# Voltage_Source.net
KiCad netlist of a schematic drawn in Altium Designer
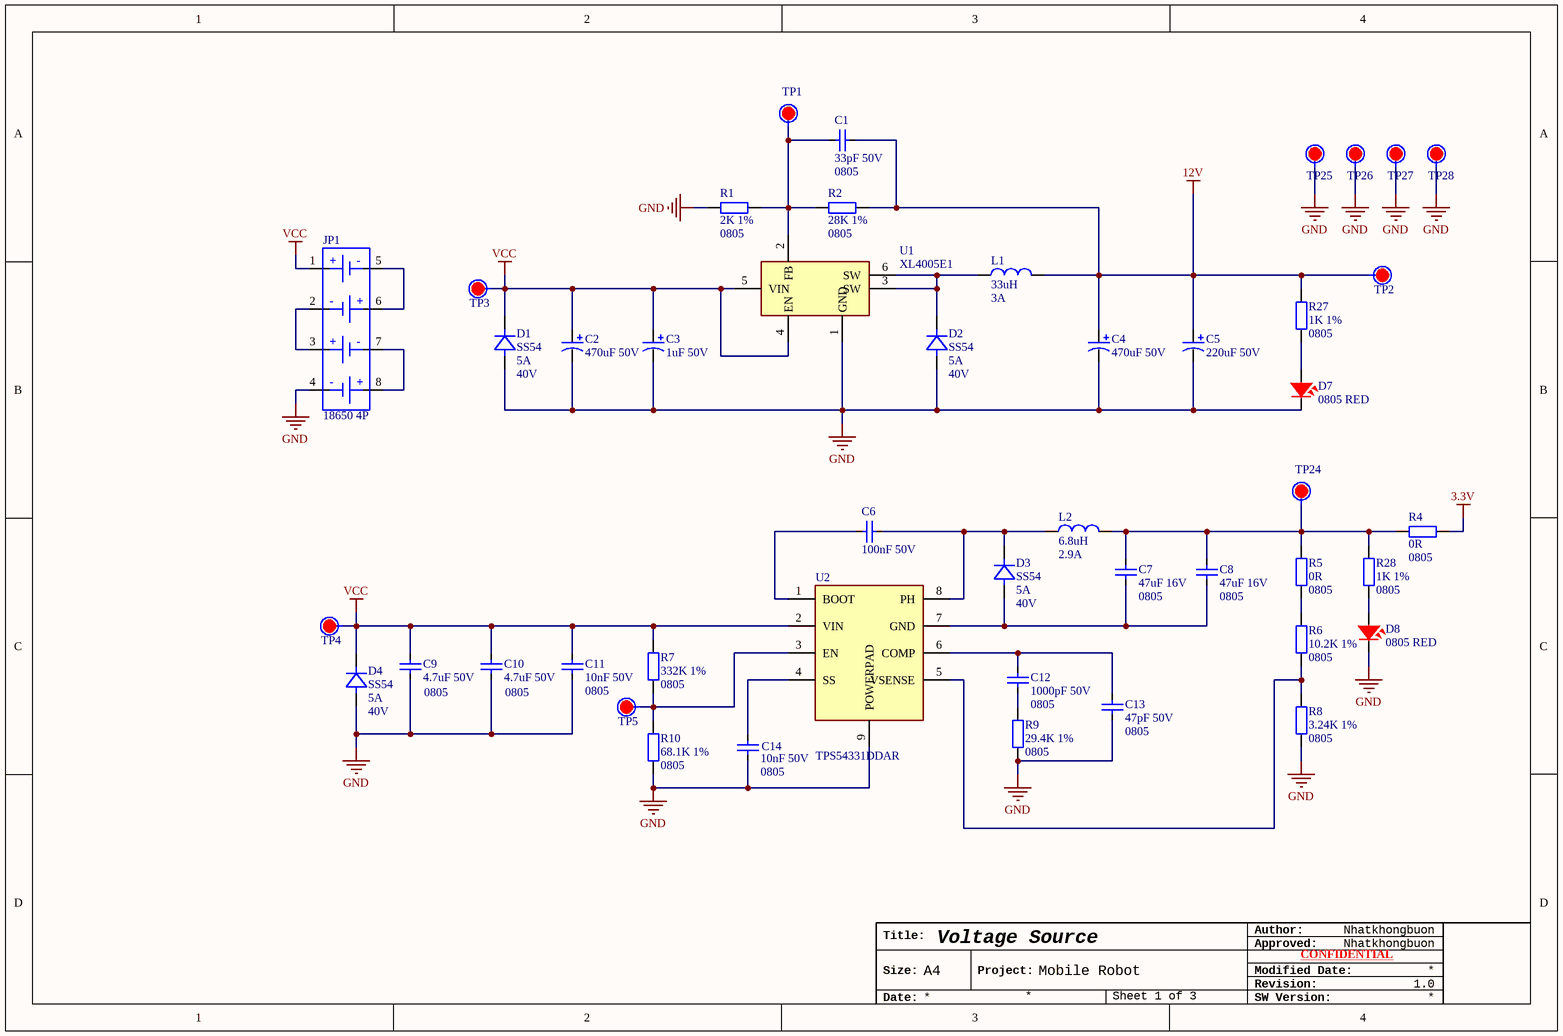
[diagram p0: Voltage Source.SchDoc]

(export (version "E")
  (design (tool "Eeschema 10.0.6"))
  (components
    (comp (ref "C1")
      (value "33pF 50V")
      (footprint "CAP_SMD_0805_NEW")
      (description "33 pF ±10% 50V Ceramic Capacitor C0G, NP0 0805 (2012 Metric)")
      (fields
        (field (name "MANUFACTURER") "KEMET")
        (field (name "MANUFACTURE PART NUMBER") "C0805C330K5GAC7800")
        (field (name "SIZE") "0805")
      )
      (libsource (lib "Capacitors") (part "C0805_MLCC_33pF_50V"))
    )
    (comp (ref "C2")
      (value "470uF 50V")
      (footprint "CAP-ALU-SMD-D12.5xL13.5")
      (description "470uF 50V ±20% SMD,D12.5xL13.5mm Aluminum Electrolytic Capacitors - SMD ROHS")
      (fields
        (field (name "MANUFACTURER") "Changzhou Huawei Elec")
        (field (name "MANUFACTURE PART NUMBER") "VT1H471MI135000CE0")
      )
      (libsource (lib "Capacitors") (part "C_ALU_470uF_50V"))
    )
    (comp (ref "C3")
      (value "1uF 50V")
      (footprint "CAP-ALU-SMD-B -NEW")
      (description "1uF 50V 7mA@120Hz ±20% SMD,D4xL5.4mm Aluminum Electrolytic Capacitors - SMD ROHS")
      (fields (field (name "MANUFACTURER") "KNSCHA") (field (name "MANUFACTURE PART NUMBER") "RST1UF50V017"))
      (libsource (lib "Capacitors") (part "C_ALU_1uF_50V_B"))
    )
    (comp (ref "C4")
      (value "470uF 50V")
      (footprint "CAP-ALU-SMD-D12.5xL13.5")
      (description "470uF 50V ±20% SMD,D12.5xL13.5mm Aluminum Electrolytic Capacitors - SMD ROHS")
      (fields
        (field (name "MANUFACTURER") "Changzhou Huawei Elec")
        (field (name "MANUFACTURE PART NUMBER") "VT1H471MI135000CE0")
      )
      (libsource (lib "Capacitors") (part "C_ALU_470uF_50V"))
    )
    (comp (ref "C5")
      (value "220uF 50V")
      (footprint "CAP-ALU-SMD-G-NEW")
      (description "220uF 50V 220mA@120Hz ±20% SMD,D10xL10.5mm Aluminum Electrolytic Capacitors - SMD ROHS")
      (fields
        (field (name "MANUFACTURER") "KNSCHA")
        (field (name "MANUFACTURE PART NUMBER") "XT220UF50V90RV0078")
      )
      (libsource (lib "Capacitors") (part "C_ALU_220uF_50V_G"))
    )
    (comp (ref "C6")
      (value "100nF 50V")
      (footprint "CAP_SMD_0805_NEW")
      (description "0.1 µF ±10% 50V Ceramic Capacitor X7R 0805 (2012 Metric)")
      (fields
        (field (name "MANUFACTURER") "YAGEO")
        (field (name "MANUFACTURE PART NUMBER") "CC0805KRX7R9BB104")
      )
      (libsource (lib "Capacitors") (part "C0805_MLCC_100nF_50V"))
    )
    (comp (ref "C7")
      (value "47uF 16V")
      (footprint "CAP_SMD_0805_NEW")
      (description "47 µF ±10% 16V Ceramic Capacitor X5R 1210 (3225 Metric)")
      (fields
        (field (name "MANUFACTURER") "Samsung Electro-Mechanics")
        (field (name "MANUFACTURE PART NUMBER") "CL32A476KOJNNNE")
        (field (name "SIZE") "0805")
      )
      (libsource (lib "Capacitors") (part "C0805_MLCC_47uF_16V"))
    )
    (comp (ref "C8")
      (value "47uF 16V")
      (footprint "CAP_SMD_0805_NEW")
      (description "47 µF ±10% 16V Ceramic Capacitor X5R 1210 (3225 Metric)")
      (fields
        (field (name "MANUFACTURER") "Samsung Electro-Mechanics")
        (field (name "MANUFACTURE PART NUMBER") "CL32A476KOJNNNE")
        (field (name "SIZE") "0805")
      )
      (libsource (lib "Capacitors") (part "C0805_MLCC_47uF_16V"))
    )
    (comp (ref "C9")
      (value "4.7uF 50V")
      (footprint "CAP_SMD_0805_NEW")
      (description "4.7 µF ±10% 50V Ceramic Capacitor X5R 0805 (2012 Metric)")
      (fields
        (field (name "MANUFACTURER") "Samsung Electro-Mechanics")
        (field (name "MANUFACTURE PART NUMBER") "CL21A475KBQNNNE")
        (field (name "SIZE") "0805")
      )
      (libsource (lib "Capacitors") (part "C0805_MLCC_4.7uF_50V"))
    )
    (comp (ref "C10")
      (value "4.7uF 50V")
      (footprint "CAP_SMD_0805_NEW")
      (description "4.7 µF ±10% 50V Ceramic Capacitor X5R 0805 (2012 Metric)")
      (fields
        (field (name "MANUFACTURER") "Samsung Electro-Mechanics")
        (field (name "MANUFACTURE PART NUMBER") "CL21A475KBQNNNE")
        (field (name "SIZE") "0805")
      )
      (libsource (lib "Capacitors") (part "C0805_MLCC_4.7uF_50V"))
    )
    (comp (ref "C11")
      (value "10nF 50V")
      (footprint "CAP_SMD_0805_NEW")
      (description "10000 pF ±10% 50V Ceramic Capacitor X7R 0805 (2012 Metric)")
      (fields
        (field (name "MANUFACTURER") "Samsung Electro-Mechanics")
        (field (name "MANUFACTURE PART NUMBER") "CL21B103KBANNNC")
        (field (name "SIZE") "0805")
      )
      (libsource (lib "Capacitors") (part "C0805_MLCC_10nF_50V"))
    )
    (comp (ref "C12")
      (value "1000pF 50V")
      (footprint "CAP_SMD_0805_NEW")
      (description "1000 pF ±10% 50V Ceramic Capacitor X7R 0805 (2012 Metric)")
      (fields
        (field (name "MANUFACTURER") "KEMET")
        (field (name "MANUFACTURE PART NUMBER") "C0805C102K5RAC7800")
        (field (name "SIZE") "0805")
      )
      (libsource (lib "Capacitors") (part "C0805_MLCC_1000pF_50V"))
    )
    (comp (ref "C13")
      (value "47pF 50V")
      (footprint "CAP_SMD_0805_NEW")
      (description "47 pF ±5% 50V Ceramic Capacitor C0G, NP0 0805 (2012 Metric)")
      (fields
        (field (name "MANUFACTURER") "YAGEO")
        (field (name "MANUFACTURE PART NUMBER") "CC0805JRNPO9BN470")
        (field (name "SIZE") "0805")
      )
      (libsource (lib "Capacitors") (part "C0805_MLCC_47pF_50V"))
    )
    (comp (ref "C14")
      (value "10nF 50V")
      (footprint "CAP_SMD_0805_NEW")
      (description "10000 pF ±10% 50V Ceramic Capacitor X7R 0805 (2012 Metric)")
      (fields
        (field (name "MANUFACTURER") "Samsung Electro-Mechanics")
        (field (name "MANUFACTURE PART NUMBER") "CL21B103KBANNNC")
        (field (name "SIZE") "0805")
      )
      (libsource (lib "Capacitors") (part "C0805_MLCC_10nF_50V"))
    )
    (comp (ref "D1")
      (value "SS54")
      (footprint "SMA")
      (description "DIODE SCHOTTKY 40V 5A SMA")
      (fields
        (field (name "MANUFACTURER") "EVVO")
        (field (name "CURRENT") "5A")
        (field (name "DC VOLTAGE") "40V")
      )
      (libsource (lib "Diode") (part "SS54"))
    )
    (comp (ref "D2")
      (value "SS54")
      (footprint "SMA")
      (description "DIODE SCHOTTKY 40V 5A SMA")
      (fields
        (field (name "MANUFACTURER") "EVVO")
        (field (name "CURRENT") "5A")
        (field (name "DC VOLTAGE") "40V")
      )
      (libsource (lib "Diode") (part "SS54"))
    )
    (comp (ref "D3")
      (value "SS54")
      (footprint "SMA")
      (description "DIODE SCHOTTKY 40V 5A SMA")
      (fields
        (field (name "MANUFACTURER") "EVVO")
        (field (name "CURRENT") "5A")
        (field (name "DC VOLTAGE") "40V")
      )
      (libsource (lib "Diode") (part "SS54"))
    )
    (comp (ref "D4")
      (value "SS54")
      (footprint "SMA")
      (description "DIODE SCHOTTKY 40V 5A SMA")
      (fields
        (field (name "MANUFACTURER") "EVVO")
        (field (name "CURRENT") "5A")
        (field (name "DC VOLTAGE") "40V")
      )
      (libsource (lib "Diode") (part "SS54"))
    )
    (comp (ref "D7")
      (value "0805 RED")
      (footprint "LED-0805-Red")
      (description "Red 625nm LED Indication - Discrete 2V 0805 (2012 Metric)")
      (fields
        (field (name "MANUFACTURER") "Würth Elektronik")
        (field (name "MANUFACTURE PART NUMBER") "150080RS75000")
      )
      (libsource (lib "LEDs") (part "LED_0805_RED"))
    )
    (comp (ref "D8")
      (value "0805 RED")
      (footprint "LED-0805-Red")
      (description "Red 625nm LED Indication - Discrete 2V 0805 (2012 Metric)")
      (fields
        (field (name "MANUFACTURER") "Würth Elektronik")
        (field (name "MANUFACTURE PART NUMBER") "150080RS75000")
      )
      (libsource (lib "LEDs") (part "LED_0805_RED"))
    )
    (comp (ref "JP1")
      (value "18650 4P")
      (footprint "18650 Holder 4P")
      (description "18650 Holder 4P")
      (libsource (lib "Connectors") (part "18650_HLD_4P"))
    )
    (comp (ref "L1")
      (value "33uH 3A")
      (footprint "L_TOR_13x7")
      (description "Toroidal Coil Inductor 33uH 3A")
      (fields (field (name "INDUCTOR") "33uH") (field (name "CURRENT") "3A"))
      (libsource (lib "Inductors") (part "L_33uH_3A"))
    )
    (comp (ref "L2")
      (value "CD74R_6.8uH")
      (footprint "CD74R")
      (description "2.9A 6.8uH ±30% SMD,7.5x7.5mm Power Inductors ROHS")
      (fields
        (field (name "MANUFACTURER") "SHOU HAN")
        (field (name "MANUFACTURE PART NUMBER") "CYH74-6.8UH")
        (field (name "INDUCTOR") "6.8uH")
        (field (name "CURRENT") "2.9A")
      )
      (libsource (lib "Inductors") (part "CD74R_6.8uH"))
    )
    (comp (ref "R1")
      (value "2K 1%")
      (footprint "RES_SMD_0805")
      (description "2 kOhms ±1% 0.125W, 1/8W Chip Resistor 0805 (2012 Metric) Automotive AEC-Q200 Thick Film")
      (fields
        (field (name "MANUFACTURER") "Panasonic Electronic Components")
        (field (name "MANUFACTURE PART NUMBER") "ERJ-6ENF2001V")
        (field (name "SIZE") "0805")
      )
      (libsource (lib "Resistors") (part "R0805_2K"))
    )
    (comp (ref "R2")
      (value "28K 1%")
      (footprint "RES_SMD_0805")
      (description "28 kOhms ±1% 0.125W, 1/8W Chip Resistor 0805 (2012 Metric) Moisture Resistant Thick Film")
      (fields
        (field (name "MANUFACTURER") "YAGEO")
        (field (name "MANUFACTURE PART NUMBER") "RC0805FR-0728KL")
        (field (name "SIZE") "0805")
      )
      (libsource (lib "Resistors") (part "R0805_28K"))
    )
    (comp (ref "R4")
      (value "0R")
      (footprint "RES_SMD_0805")
      (description "0 Ohms Jumper Chip Resistor 0805 (2012 Metric) Automotive AEC-Q200 Thick Film")
      (fields
        (field (name "MANUFACTURER") "Vishay Dale")
        (field (name "MANUFACTURE PART NUMBER") "CRCW08050000Z0EA")
        (field (name "SIZE") "0805")
      )
      (libsource (lib "Resistors") (part "R0805_0R"))
    )
    (comp (ref "R5")
      (value "0R")
      (footprint "RES_SMD_0805")
      (description "0 Ohms Jumper Chip Resistor 0805 (2012 Metric) Automotive AEC-Q200 Thick Film")
      (fields
        (field (name "MANUFACTURER") "Vishay Dale")
        (field (name "MANUFACTURE PART NUMBER") "CRCW08050000Z0EA")
        (field (name "SIZE") "0805")
      )
      (libsource (lib "Resistors") (part "R0805_0R"))
    )
    (comp (ref "R6")
      (value "10.2K 1%")
      (footprint "RES_SMD_0805")
      (description "10.2 kOhms ±1% 0.125W, 1/8W Chip Resistor 0805 (2012 Metric) Moisture Resistant Thick Film")
      (fields
        (field (name "MANUFACTURER") "YAGEO")
        (field (name "MANUFACTURE PART NUMBER") "RC0805FR-0710K2L")
        (field (name "SIZE") "0805")
      )
      (libsource (lib "Resistors") (part "R0805_10.2K"))
    )
    (comp (ref "R7")
      (value "332K 1%")
      (footprint "RES_SMD_0805")
      (description "332 kOhms ±1% 0.125W, 1/8W Chip Resistor 0805 (2012 Metric) Moisture Resistant Thick Film")
      (fields
        (field (name "MANUFACTURER") "YAGEO")
        (field (name "MANUFACTURE PART NUMBER") "RC0805FR-07332KL")
        (field (name "SIZE") "0805")
      )
      (libsource (lib "Resistors") (part "R0805_332K"))
    )
    (comp (ref "R8")
      (value "3.24K 1%")
      (footprint "RES_SMD_0805")
      (description "3.24 kOhms ±1% 0.125W, 1/8W Chip Resistor 0805 (2012 Metric) Moisture Resistant Thick Film")
      (fields
        (field (name "MANUFACTURER") "YAGEO")
        (field (name "MANUFACTURE PART NUMBER") "RC0805FR-073K24L")
        (field (name "SIZE") "0805")
      )
      (libsource (lib "Resistors") (part "R0805_3.24K"))
    )
    (comp (ref "R9")
      (value "29.4K 1%")
      (footprint "RES_SMD_0805")
      (description "29.4 kOhms ±1% 0.125W, 1/8W Chip Resistor 0805 (2012 Metric) Moisture Resistant Thick Film")
      (fields
        (field (name "MANUFACTURER") "YAGEO")
        (field (name "MANUFACTURE PART NUMBER") "RC0805FR-0729K4L")
        (field (name "SIZE") "0805")
      )
      (libsource (lib "Resistors") (part "R0805_29.4K"))
    )
    (comp (ref "R10")
      (value "68.1K 1%")
      (footprint "RES_SMD_0805")
      (description "68.1 kOhms ±1% 0.125W, 1/8W Chip Resistor 0805 (2012 Metric) Moisture Resistant Thick Film")
      (fields
        (field (name "MANUFACTURER") "YAGEO")
        (field (name "MANUFACTURE PART NUMBER") "RC0805FR-0768K1L")
        (field (name "SIZE") "0805")
      )
      (libsource (lib "Resistors") (part "R0805_68.1K"))
    )
    (comp (ref "R27")
      (value "1K 1%")
      (footprint "RES_SMD_0805")
      (description "1 kOhms ±1% 0.125W, 1/8W Chip Resistor 0805 (2012 Metric) Moisture Resistant Thick Film")
      (fields
        (field (name "MANUFACTURER") "YAGEO")
        (field (name "MANUFACTURE PART NUMBER") "311-1.00KCRCT-ND")
        (field (name "SIZE") "0805")
      )
      (libsource (lib "Resistors") (part "R0805_1K"))
    )
    (comp (ref "R28")
      (value "1K 1%")
      (footprint "RES_SMD_0805")
      (description "1 kOhms ±1% 0.125W, 1/8W Chip Resistor 0805 (2012 Metric) Moisture Resistant Thick Film")
      (fields
        (field (name "MANUFACTURER") "YAGEO")
        (field (name "MANUFACTURE PART NUMBER") "311-1.00KCRCT-ND")
        (field (name "SIZE") "0805")
      )
      (libsource (lib "Resistors") (part "R0805_1K"))
    )
    (comp (ref "TP1")
      (value "Test Point")
      (footprint "TEST_POINT")
      (libsource (lib "Connectors") (part "TEST_POINT"))
    )
    (comp (ref "TP2")
      (value "Test Point")
      (footprint "TEST_POINT")
      (libsource (lib "Connectors") (part "TEST_POINT"))
    )
    (comp (ref "TP3")
      (value "Test Point")
      (footprint "TEST_POINT")
      (libsource (lib "Connectors") (part "TEST_POINT"))
    )
    (comp (ref "TP4")
      (value "Test Point")
      (footprint "TEST_POINT")
      (libsource (lib "Connectors") (part "TEST_POINT"))
    )
    (comp (ref "TP5")
      (value "Test Point")
      (footprint "TEST_POINT")
      (libsource (lib "Connectors") (part "TEST_POINT"))
    )
    (comp (ref "TP24")
      (value "Test Point")
      (footprint "TEST_POINT")
      (libsource (lib "Connectors") (part "TEST_POINT"))
    )
    (comp (ref "TP25")
      (value "Test Point")
      (footprint "TEST_POINT")
      (libsource (lib "Connectors") (part "TEST_POINT"))
    )
    (comp (ref "TP26")
      (value "Test Point")
      (footprint "TEST_POINT")
      (libsource (lib "Connectors") (part "TEST_POINT"))
    )
    (comp (ref "TP27")
      (value "Test Point")
      (footprint "TEST_POINT")
      (libsource (lib "Connectors") (part "TEST_POINT"))
    )
    (comp (ref "TP28")
      (value "Test Point")
      (footprint "TEST_POINT")
      (libsource (lib "Connectors") (part "TEST_POINT"))
    )
    (comp (ref "U1")
      (value "XL4005E1")
      (footprint "TO263-5")
      (description "Step-down type 800mV~30V 5A 5V~32V TO-263-5 DC-DC Converters ROHS")
      (fields (field (name "MANUFACTURER") "XLSEMI"))
      (libsource (lib "Voltage_Regulators") (part "XL4005E1"))
    )
    (comp (ref "U2")
      (value "TPS54331DDAR")
      (footprint "TPS54531DDAR")
      (fields (field (name "MANUFACTURER") "Texas Instruments"))
      (libsource (lib "Voltage_Regulators") (part "TPS54331DDAR"))
    )
  )
  (nets
    (net (code "1") (name "3.3V") (class "Default")
      (node (ref "R4") (pin "1") (pinfunction "1_1") (pintype "passive"))
    )
    (net (code "2") (name "12V") (class "Default")
      (node (ref "C1") (pin "2") (pinfunction "2_2") (pintype "passive"))
      (node (ref "C4") (pin "1") (pinfunction "1_1") (pintype "passive"))
      (node (ref "C5") (pin "1") (pinfunction "1_1") (pintype "passive"))
      (node (ref "L1") (pin "2") (pinfunction "2_2") (pintype "passive"))
      (node (ref "R2") (pin "2") (pinfunction "2_2") (pintype "passive"))
      (node (ref "R27") (pin "1") (pinfunction "1_1") (pintype "passive"))
      (node (ref "TP2") (pin "1") (pinfunction "1_1") (pintype "passive"))
    )
    (net (code "3") (name "GND") (class "Default")
      (node (ref "C10") (pin "1") (pinfunction "1_1") (pintype "passive"))
      (node (ref "C11") (pin "1") (pinfunction "1_1") (pintype "passive"))
      (node (ref "C13") (pin "1") (pinfunction "1_1") (pintype "passive"))
      (node (ref "C14") (pin "1") (pinfunction "1_1") (pintype "passive"))
      (node (ref "C2") (pin "2") (pinfunction "2_2") (pintype "passive"))
      (node (ref "C3") (pin "2") (pinfunction "2_2") (pintype "passive"))
      (node (ref "C4") (pin "2") (pinfunction "2_2") (pintype "passive"))
      (node (ref "C5") (pin "2") (pinfunction "2_2") (pintype "passive"))
      (node (ref "C9") (pin "1") (pinfunction "1_1") (pintype "passive"))
      (node (ref "D1") (pin "A") (pinfunction "A_A") (pintype "passive"))
      (node (ref "D2") (pin "A") (pinfunction "A_A") (pintype "passive"))
      (node (ref "D4") (pin "A") (pinfunction "A_A") (pintype "passive"))
      (node (ref "D7") (pin "2") (pinfunction "2_2") (pintype "passive"))
      (node (ref "D8") (pin "2") (pinfunction "2_2") (pintype "passive"))
      (node (ref "JP1") (pin "4") (pinfunction "4_4") (pintype "passive"))
      (node (ref "R1") (pin "1") (pinfunction "1_1") (pintype "passive"))
      (node (ref "R10") (pin "1") (pinfunction "1_1") (pintype "passive"))
      (node (ref "R8") (pin "1") (pinfunction "1_1") (pintype "passive"))
      (node (ref "R9") (pin "1") (pinfunction "1_1") (pintype "passive"))
      (node (ref "TP25") (pin "1") (pinfunction "1_1") (pintype "passive"))
      (node (ref "TP26") (pin "1") (pinfunction "1_1") (pintype "passive"))
      (node (ref "TP27") (pin "1") (pinfunction "1_1") (pintype "passive"))
      (node (ref "TP28") (pin "1") (pinfunction "1_1") (pintype "passive"))
      (node (ref "U1") (pin "1") (pinfunction "GND_1") (pintype "passive"))
      (node (ref "U2") (pin "9") (pinfunction "POWERPAD_9") (pintype "passive"))
    )
    (net (code "4") (name "Net-(C7-Pad2)") (class "Default")
      (node (ref "C7") (pin "2") (pinfunction "2_2") (pintype "passive"))
      (node (ref "C8") (pin "2") (pinfunction "2_2") (pintype "passive"))
      (node (ref "L2") (pin "2") (pinfunction "2_2") (pintype "passive"))
      (node (ref "R28") (pin "1") (pinfunction "1_1") (pintype "passive"))
      (node (ref "R4") (pin "2") (pinfunction "2_2") (pintype "passive"))
      (node (ref "R5") (pin "2") (pinfunction "2_2") (pintype "passive"))
      (node (ref "TP24") (pin "1") (pinfunction "1_1") (pintype "passive"))
    )
    (net (code "5") (name "Net-(C12-Pad1)") (class "Default")
      (node (ref "C12") (pin "1") (pinfunction "1_1") (pintype "passive"))
      (node (ref "R9") (pin "2") (pinfunction "2_2") (pintype "passive"))
    )
    (net (code "6") (name "Net-(D2-PadC)") (class "Default")
      (node (ref "D2") (pin "C") (pinfunction "C_C") (pintype "passive"))
      (node (ref "L1") (pin "1") (pinfunction "1_1") (pintype "passive"))
      (node (ref "U1") (pin "3") (pinfunction "SW_3") (pintype "passive"))
      (node (ref "U1") (pin "6") (pinfunction "SW_6") (pintype "passive"))
    )
    (net (code "7") (name "Net-(D7-Pad1)") (class "Default")
      (node (ref "D7") (pin "1") (pinfunction "1_1") (pintype "passive"))
      (node (ref "R27") (pin "2") (pinfunction "2_2") (pintype "passive"))
    )
    (net (code "8") (name "Net-(D8-Pad1)") (class "Default")
      (node (ref "D8") (pin "1") (pinfunction "1_1") (pintype "passive"))
      (node (ref "R28") (pin "2") (pinfunction "2_2") (pintype "passive"))
    )
    (net (code "9") (name "Net-(JP1-Pad2)") (class "Default")
      (node (ref "JP1") (pin "2") (pinfunction "2_2") (pintype "passive"))
      (node (ref "JP1") (pin "3") (pinfunction "3_3") (pintype "passive"))
    )
    (net (code "10") (name "Net-(JP1-Pad5)") (class "Default")
      (node (ref "JP1") (pin "5") (pinfunction "5_5") (pintype "passive"))
      (node (ref "JP1") (pin "6") (pinfunction "6_6") (pintype "passive"))
    )
    (net (code "11") (name "Net-(JP1-Pad7)") (class "Default")
      (node (ref "JP1") (pin "7") (pinfunction "7_7") (pintype "passive"))
      (node (ref "JP1") (pin "8") (pinfunction "8_8") (pintype "passive"))
    )
    (net (code "12") (name "Net-(R5-Pad1)") (class "Default")
      (node (ref "R5") (pin "1") (pinfunction "1_1") (pintype "passive"))
      (node (ref "R6") (pin "2") (pinfunction "2_2") (pintype "passive"))
    )
    (net (code "13") (name "Net-(U1-FB)") (class "Default")
      (node (ref "C1") (pin "1") (pinfunction "1_1") (pintype "passive"))
      (node (ref "R1") (pin "2") (pinfunction "2_2") (pintype "passive"))
      (node (ref "R2") (pin "1") (pinfunction "1_1") (pintype "passive"))
      (node (ref "TP1") (pin "1") (pinfunction "1_1") (pintype "passive"))
      (node (ref "U1") (pin "2") (pinfunction "FB_2") (pintype "passive"))
    )
    (net (code "14") (name "Net-(U2-BOOT)") (class "Default")
      (node (ref "C6") (pin "1") (pinfunction "1_1") (pintype "passive"))
      (node (ref "U2") (pin "1") (pinfunction "BOOT_1") (pintype "passive"))
    )
    (net (code "15") (name "Net-(U2-COMP)") (class "Default")
      (node (ref "C12") (pin "2") (pinfunction "2_2") (pintype "passive"))
      (node (ref "C13") (pin "2") (pinfunction "2_2") (pintype "passive"))
      (node (ref "U2") (pin "6") (pinfunction "COMP_6") (pintype "passive"))
    )
    (net (code "16") (name "Net-(U2-EN)") (class "Default")
      (node (ref "R10") (pin "2") (pinfunction "2_2") (pintype "passive"))
      (node (ref "R7") (pin "1") (pinfunction "1_1") (pintype "passive"))
      (node (ref "TP5") (pin "1") (pinfunction "1_1") (pintype "passive"))
      (node (ref "U2") (pin "3") (pinfunction "EN_3") (pintype "passive"))
    )
    (net (code "17") (name "Net-(U2-GND)") (class "Default")
      (node (ref "C7") (pin "1") (pinfunction "1_1") (pintype "passive"))
      (node (ref "C8") (pin "1") (pinfunction "1_1") (pintype "passive"))
      (node (ref "D3") (pin "A") (pinfunction "A_A") (pintype "passive"))
      (node (ref "U2") (pin "7") (pinfunction "GND_7") (pintype "passive"))
    )
    (net (code "18") (name "Net-(U2-PH)") (class "Default")
      (node (ref "C6") (pin "2") (pinfunction "2_2") (pintype "passive"))
      (node (ref "D3") (pin "C") (pinfunction "C_C") (pintype "passive"))
      (node (ref "L2") (pin "1") (pinfunction "1_1") (pintype "passive"))
      (node (ref "U2") (pin "8") (pinfunction "PH_8") (pintype "passive"))
    )
    (net (code "19") (name "Net-(U2-SS)") (class "Default")
      (node (ref "C14") (pin "2") (pinfunction "2_2") (pintype "passive"))
      (node (ref "U2") (pin "4") (pinfunction "SS_4") (pintype "passive"))
    )
    (net (code "20") (name "Net-(U2-VSENSE)") (class "Default")
      (node (ref "R6") (pin "1") (pinfunction "1_1") (pintype "passive"))
      (node (ref "R8") (pin "2") (pinfunction "2_2") (pintype "passive"))
      (node (ref "U2") (pin "5") (pinfunction "VSENSE_5") (pintype "passive"))
    )
    (net (code "21") (name "VCC") (class "Default")
      (node (ref "C10") (pin "2") (pinfunction "2_2") (pintype "passive"))
      (node (ref "C11") (pin "2") (pinfunction "2_2") (pintype "passive"))
      (node (ref "C2") (pin "1") (pinfunction "1_1") (pintype "passive"))
      (node (ref "C3") (pin "1") (pinfunction "1_1") (pintype "passive"))
      (node (ref "C9") (pin "2") (pinfunction "2_2") (pintype "passive"))
      (node (ref "D1") (pin "C") (pinfunction "C_C") (pintype "passive"))
      (node (ref "D4") (pin "C") (pinfunction "C_C") (pintype "passive"))
      (node (ref "JP1") (pin "1") (pinfunction "1_1") (pintype "passive"))
      (node (ref "R7") (pin "2") (pinfunction "2_2") (pintype "passive"))
      (node (ref "TP3") (pin "1") (pinfunction "1_1") (pintype "passive"))
      (node (ref "TP4") (pin "1") (pinfunction "1_1") (pintype "passive"))
      (node (ref "U1") (pin "4") (pinfunction "EN_4") (pintype "passive"))
      (node (ref "U1") (pin "5") (pinfunction "VIN_5") (pintype "passive"))
      (node (ref "U2") (pin "2") (pinfunction "VIN_2") (pintype "passive"))
    )
  )
)
